# Fliege_Notch_Sim.net
KiCad netlist of a schematic drawn in Altium Designer
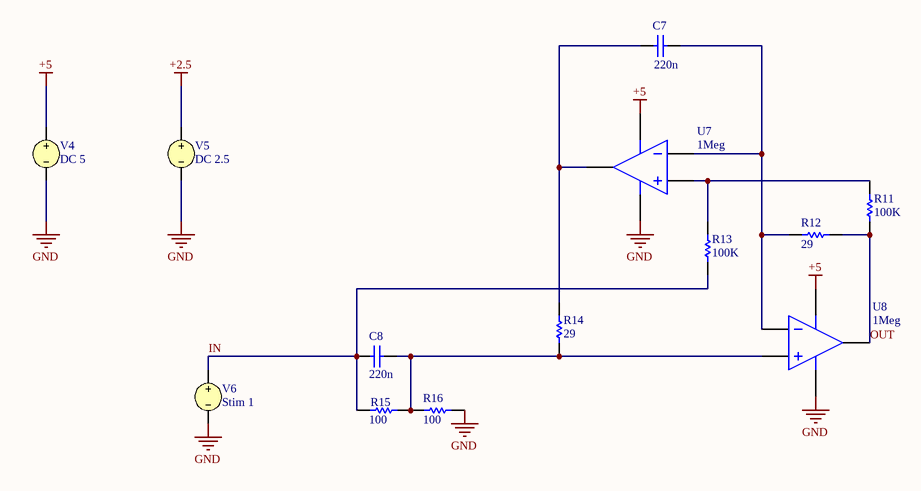
[diagram p0: Fliege_Notch_Sim.SchDoc]

(export (version "E")
  (design (tool "Eeschema 10.0.6"))
  (components
    (comp (ref "C7")
      (value "220n")
      (description "Capacitor")
      (libsource (lib "Simulation Generic Components") (part "Capacitor"))
    )
    (comp (ref "C8")
      (value "220n")
      (description "Capacitor")
      (libsource (lib "Simulation Generic Components") (part "Capacitor"))
    )
    (comp (ref "R11")
      (value "100K")
      (description "Resistor")
      (libsource (lib "Simulation Generic Components") (part "Resistor"))
    )
    (comp (ref "R12")
      (value "29")
      (description "Resistor")
      (libsource (lib "Simulation Generic Components") (part "Resistor"))
    )
    (comp (ref "R13")
      (value "100K")
      (description "Resistor")
      (libsource (lib "Simulation Generic Components") (part "Resistor"))
    )
    (comp (ref "R14")
      (value "29")
      (description "Resistor")
      (libsource (lib "Simulation Generic Components") (part "Resistor"))
    )
    (comp (ref "R15")
      (value "100")
      (description "Resistor")
      (libsource (lib "Simulation Generic Components") (part "Resistor"))
    )
    (comp (ref "R16")
      (value "100")
      (description "Resistor")
      (libsource (lib "Simulation Generic Components") (part "Resistor"))
    )
    (comp (ref "U7")
      (value "Ideal Operational Amplifier")
      (fields (field (name "GAIN") "1Meg"))
      (libsource (lib "Simulation Generic Components") (part "OpAmp with power terminals"))
    )
    (comp (ref "U8")
      (value "Ideal Operational Amplifier")
      (fields (field (name "GAIN") "1Meg"))
      (libsource (lib "Simulation Generic Components") (part "OpAmp with power terminals"))
    )
    (comp (ref "V4")
      (value "DC 5")
      (description "Voltage Source")
      (fields (field (name "PUBLISHER") "Altium Limited"))
      (libsource (lib "Simulation Generic Components") (part "VSRC"))
    )
    (comp (ref "V5")
      (value "DC 2.5")
      (description "Voltage Source")
      (fields (field (name "PUBLISHER") "Altium Limited"))
      (libsource (lib "Simulation Generic Components") (part "VSRC"))
    )
    (comp (ref "V6")
      (value "Stim 1")
      (description "Voltage Source")
      (fields (field (name "PUBLISHER") "Altium Limited"))
      (libsource (lib "Simulation Generic Components") (part "VSRC"))
    )
  )
  (nets
    (net (code "1") (name "+2.5") (class "Default")
      (node (ref "V5") (pin "1") (pinfunction "1_1") (pintype "passive"))
    )
    (net (code "2") (name "+5") (class "Default")
      (node (ref "U7") (pin "4") (pinfunction "V+_4") (pintype "power_in"))
      (node (ref "U8") (pin "4") (pinfunction "V+_4") (pintype "power_in"))
      (node (ref "V4") (pin "1") (pinfunction "1_1") (pintype "passive"))
    )
    (net (code "3") (name "/IN") (class "Default")
      (node (ref "C8") (pin "1") (pinfunction "1_1") (pintype "passive"))
      (node (ref "R13") (pin "2") (pinfunction "2_2") (pintype "passive"))
      (node (ref "R15") (pin "1") (pinfunction "1_1") (pintype "passive"))
      (node (ref "V6") (pin "1") (pinfunction "1_1") (pintype "passive"))
    )
    (net (code "4") (name "/OUT") (class "Default")
      (node (ref "R11") (pin "2") (pinfunction "2_2") (pintype "passive"))
      (node (ref "R12") (pin "1") (pinfunction "1_1") (pintype "passive"))
      (node (ref "U8") (pin "3") (pinfunction "OUT_3") (pintype "passive"))
    )
    (net (code "5") (name "GND") (class "Default")
      (node (ref "R16") (pin "1") (pinfunction "1_1") (pintype "passive"))
      (node (ref "U7") (pin "5") (pinfunction "V-_5") (pintype "power_in"))
      (node (ref "U8") (pin "5") (pinfunction "V-_5") (pintype "power_in"))
      (node (ref "V4") (pin "2") (pinfunction "2_2") (pintype "passive"))
      (node (ref "V5") (pin "2") (pinfunction "2_2") (pintype "passive"))
      (node (ref "V6") (pin "2") (pinfunction "2_2") (pintype "passive"))
    )
    (net (code "6") (name "Net-(U7-IN+)") (class "Default")
      (node (ref "R11") (pin "1") (pinfunction "1_1") (pintype "passive"))
      (node (ref "R13") (pin "1") (pinfunction "1_1") (pintype "passive"))
      (node (ref "U7") (pin "2") (pinfunction "IN+_2") (pintype "passive"))
    )
    (net (code "7") (name "Net-(U7-IN-)") (class "Default")
      (node (ref "C7") (pin "2") (pinfunction "2_2") (pintype "passive"))
      (node (ref "R12") (pin "2") (pinfunction "2_2") (pintype "passive"))
      (node (ref "U7") (pin "1") (pinfunction "IN-_1") (pintype "passive"))
      (node (ref "U8") (pin "1") (pinfunction "IN-_1") (pintype "passive"))
    )
    (net (code "8") (name "Net-(U7-OUT)") (class "Default")
      (node (ref "C7") (pin "1") (pinfunction "1_1") (pintype "passive"))
      (node (ref "R14") (pin "1") (pinfunction "1_1") (pintype "passive"))
      (node (ref "U7") (pin "3") (pinfunction "OUT_3") (pintype "passive"))
    )
    (net (code "9") (name "Net-(U8-IN+)") (class "Default")
      (node (ref "C8") (pin "2") (pinfunction "2_2") (pintype "passive"))
      (node (ref "R14") (pin "2") (pinfunction "2_2") (pintype "passive"))
      (node (ref "R15") (pin "2") (pinfunction "2_2") (pintype "passive"))
      (node (ref "R16") (pin "2") (pinfunction "2_2") (pintype "passive"))
      (node (ref "U8") (pin "2") (pinfunction "IN+_2") (pintype "passive"))
    )
  )
)
